# bass_filter.net
KiCad netlist of a schematic drawn in EAGLE
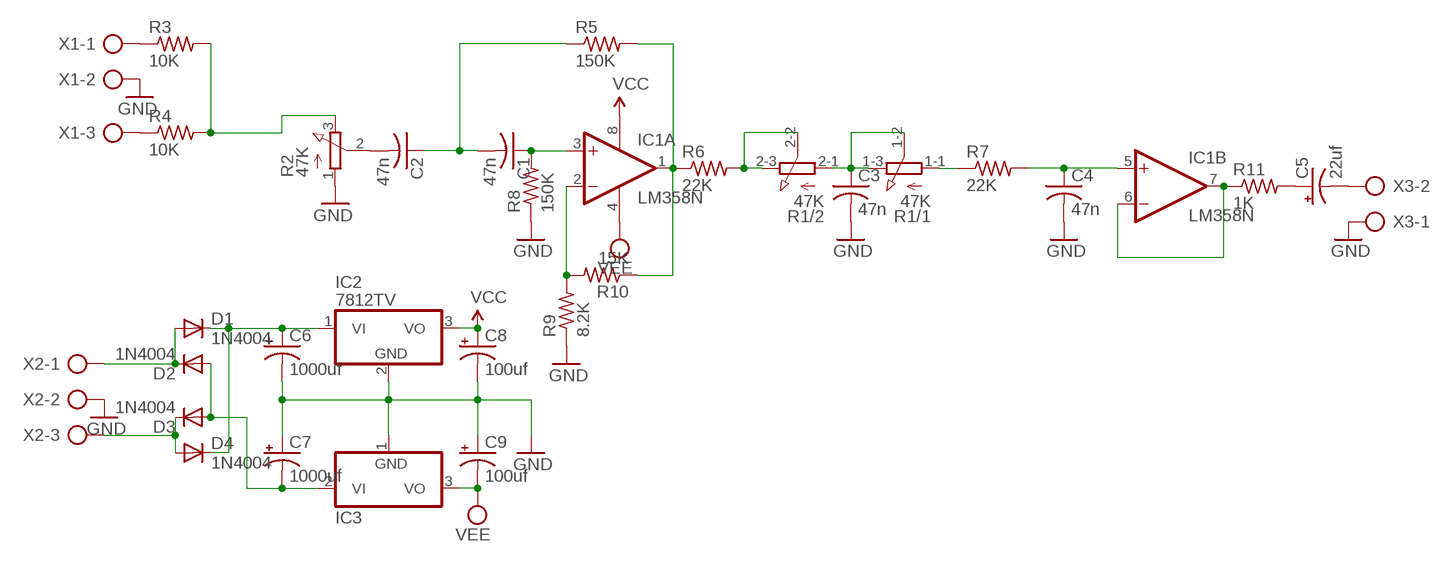
[diagram p0: schematic, sheet 1]

(export (version "E")
  (design (tool "Eeschema 10.0.6"))
  (components
    (comp (ref "C1")
      (value "47n")
      (footprint "eagle-import:C050-045X075")
      (libsource (lib "eagle-import") (part "C-US050-045X075"))
    )
    (comp (ref "C2")
      (value "47n")
      (footprint "eagle-import:C050-045X075")
      (libsource (lib "eagle-import") (part "C-US050-045X075"))
    )
    (comp (ref "C3")
      (value "47n")
      (footprint "eagle-import:C050-045X075")
      (libsource (lib "eagle-import") (part "C-US050-045X075"))
    )
    (comp (ref "C4")
      (value "47n")
      (footprint "eagle-import:C050-045X075")
      (libsource (lib "eagle-import") (part "C-US050-045X075"))
    )
    (comp (ref "C5")
      (value "22uf")
      (footprint "eagle-import:E2,5-6E")
      (libsource (lib "eagle-import") (part "CPOL-USE2,5-6E"))
    )
    (comp (ref "C6")
      (value "1000uf")
      (footprint "eagle-import:E5-13")
      (libsource (lib "eagle-import") (part "CPOL-USE5-13"))
    )
    (comp (ref "C7")
      (value "1000uf")
      (footprint "eagle-import:E5-13")
      (libsource (lib "eagle-import") (part "CPOL-USE5-13"))
    )
    (comp (ref "C8")
      (value "100uf")
      (footprint "eagle-import:E2,5-6")
      (libsource (lib "eagle-import") (part "CPOL-USE2.5-6"))
    )
    (comp (ref "C9")
      (value "100uf")
      (footprint "eagle-import:E2,5-6")
      (libsource (lib "eagle-import") (part "CPOL-USE2.5-6"))
    )
    (comp (ref "D1")
      (value "1N4004")
      (footprint "eagle-import:DO41-10")
      (libsource (lib "eagle-import") (part "1N4004"))
    )
    (comp (ref "D2")
      (value "1N4004")
      (footprint "eagle-import:DO41-10")
      (libsource (lib "eagle-import") (part "1N4004"))
    )
    (comp (ref "D3")
      (value "1N4004")
      (footprint "eagle-import:DO41-10")
      (libsource (lib "eagle-import") (part "1N4004"))
    )
    (comp (ref "D4")
      (value "1N4004")
      (footprint "eagle-import:DO41-10")
      (libsource (lib "eagle-import") (part "1N4004"))
    )
    (comp (ref "IC1")
      (value "LM358N")
      (footprint "eagle-import:DIL08")
      (libsource (lib "eagle-import") (part "LM358N"))
    )
    (comp (ref "IC2")
      (value "7812TV")
      (footprint "eagle-import:TO220V")
      (libsource (lib "eagle-import") (part "78TV12"))
    )
    (comp (ref "IC3")
      (value "7912T")
      (footprint "eagle-import:TO220H")
      (libsource (lib "eagle-import") (part "79T12"))
    )
    (comp (ref "R1")
      (value "47K")
      (footprint "eagle-import:3RP_1610G")
      (libsource (lib "eagle-import") (part "3RP/1610G"))
    )
    (comp (ref "R2")
      (value "47K")
      (footprint "eagle-import:3RP_1610N")
      (libsource (lib "eagle-import") (part "3RP/1610N"))
    )
    (comp (ref "R3")
      (value "10K")
      (footprint "eagle-import:0805-THM")
      (libsource (lib "eagle-import") (part "FLIPFLOP-RES"))
    )
    (comp (ref "R4")
      (value "10K")
      (footprint "eagle-import:0805-THM")
      (libsource (lib "eagle-import") (part "FLIPFLOP-RES"))
    )
    (comp (ref "R5")
      (value "150K")
      (footprint "eagle-import:0805-THM")
      (libsource (lib "eagle-import") (part "FLIPFLOP-RES"))
    )
    (comp (ref "R6")
      (value "22K")
      (footprint "eagle-import:0805-THM")
      (libsource (lib "eagle-import") (part "FLIPFLOP-RES"))
    )
    (comp (ref "R7")
      (value "22K")
      (footprint "eagle-import:0805-THM")
      (libsource (lib "eagle-import") (part "FLIPFLOP-RES"))
    )
    (comp (ref "R8")
      (value "150K")
      (footprint "eagle-import:0805-THM")
      (libsource (lib "eagle-import") (part "FLIPFLOP-RES"))
    )
    (comp (ref "R9")
      (value "8.2K")
      (footprint "eagle-import:0805-THM")
      (libsource (lib "eagle-import") (part "FLIPFLOP-RES"))
    )
    (comp (ref "R10")
      (value "15K")
      (footprint "eagle-import:0805-THM")
      (libsource (lib "eagle-import") (part "FLIPFLOP-RES"))
    )
    (comp (ref "R11")
      (value "1K")
      (footprint "eagle-import:0805-THM")
      (libsource (lib "eagle-import") (part "FLIPFLOP-RES"))
    )
    (comp (ref "X1")
      (value "AK300/3")
      (footprint "eagle-import:AK300_3")
      (libsource (lib "eagle-import") (part "AK300/3"))
    )
    (comp (ref "X2")
      (value "AK300/3")
      (footprint "eagle-import:AK300_3")
      (libsource (lib "eagle-import") (part "AK300/3"))
    )
    (comp (ref "X3")
      (value "AK300/2")
      (footprint "eagle-import:AK300_2")
      (libsource (lib "eagle-import") (part "AK300/2"))
    )
  )
  (nets
    (net (code "1") (name "GND") (class "Default")
      (node (ref "C3") (pin "2") (pinfunction "2_2") (pintype "passive"))
      (node (ref "C4") (pin "2") (pinfunction "2_2") (pintype "passive"))
      (node (ref "C6") (pin "-") (pinfunction "-_-") (pintype "passive"))
      (node (ref "C7") (pin "+") (pinfunction "+_+") (pintype "passive"))
      (node (ref "C8") (pin "-") (pinfunction "-_-") (pintype "passive"))
      (node (ref "C9") (pin "+") (pinfunction "+_+") (pintype "passive"))
      (node (ref "IC2") (pin "2") (pinfunction "GND_2") (pintype "passive"))
      (node (ref "IC3") (pin "1") (pinfunction "GND_1") (pintype "passive"))
      (node (ref "R2") (pin "1") (pinfunction "A_1") (pintype "passive"))
      (node (ref "R8") (pin "1") (pinfunction "1_1") (pintype "passive"))
      (node (ref "R9") (pin "1") (pinfunction "1_1") (pintype "passive"))
      (node (ref "X1") (pin "2") (pinfunction "KL_2") (pintype "passive"))
      (node (ref "X2") (pin "2") (pinfunction "KL_2") (pintype "passive"))
      (node (ref "X3") (pin "1") (pinfunction "KL_1") (pintype "passive"))
    )
    (net (code "2") (name "Net-(C1-Pad2)") (class "Default")
      (node (ref "C1") (pin "2") (pinfunction "2_2") (pintype "passive"))
      (node (ref "C2") (pin "1") (pinfunction "1_1") (pintype "passive"))
      (node (ref "R5") (pin "1") (pinfunction "1_1") (pintype "passive"))
    )
    (net (code "3") (name "Net-(C5-Pad+)") (class "Default")
      (node (ref "C5") (pin "+") (pinfunction "+_+") (pintype "passive"))
      (node (ref "R11") (pin "2") (pinfunction "2_2") (pintype "passive"))
    )
    (net (code "4") (name "Net-(IC1A-+IN)") (class "Default")
      (node (ref "C1") (pin "1") (pinfunction "1_1") (pintype "passive"))
      (node (ref "IC1") (pin "3") (pinfunction "+IN_3") (pintype "input"))
      (node (ref "R8") (pin "2") (pinfunction "2_2") (pintype "passive"))
    )
    (net (code "5") (name "Net-(IC1A--IN)") (class "Default")
      (node (ref "IC1") (pin "2") (pinfunction "-IN_2") (pintype "input"))
      (node (ref "R10") (pin "2") (pinfunction "2_2") (pintype "passive"))
      (node (ref "R9") (pin "2") (pinfunction "2_2") (pintype "passive"))
    )
    (net (code "6") (name "Net-(IC1A-OUT)") (class "Default")
      (node (ref "IC1") (pin "1") (pinfunction "OUT_1") (pintype "output"))
      (node (ref "R10") (pin "1") (pinfunction "1_1") (pintype "passive"))
      (node (ref "R5") (pin "2") (pinfunction "2_2") (pintype "passive"))
      (node (ref "R6") (pin "1") (pinfunction "1_1") (pintype "passive"))
    )
    (net (code "7") (name "Net-(IC1B-+IN)") (class "Default")
      (node (ref "C4") (pin "1") (pinfunction "1_1") (pintype "passive"))
      (node (ref "IC1") (pin "5") (pinfunction "+IN_5") (pintype "input"))
      (node (ref "R7") (pin "2") (pinfunction "2_2") (pintype "passive"))
    )
    (net (code "8") (name "Net-(IC1B--IN)") (class "Default")
      (node (ref "IC1") (pin "6") (pinfunction "-IN_6") (pintype "input"))
      (node (ref "IC1") (pin "7") (pinfunction "OUT_7") (pintype "output"))
      (node (ref "R11") (pin "1") (pinfunction "1_1") (pintype "passive"))
    )
    (net (code "9") (name "Net-(IC2-VI)") (class "Default")
      (node (ref "C6") (pin "+") (pinfunction "+_+") (pintype "passive"))
      (node (ref "D1") (pin "C") (pinfunction "C_C") (pintype "passive"))
      (node (ref "D4") (pin "C") (pinfunction "C_C") (pintype "passive"))
      (node (ref "IC2") (pin "1") (pinfunction "VI_1") (pintype "input"))
    )
    (net (code "10") (name "Net-(IC3-VI)") (class "Default")
      (node (ref "C7") (pin "-") (pinfunction "-_-") (pintype "passive"))
      (node (ref "D2") (pin "A") (pinfunction "A_A") (pintype "passive"))
      (node (ref "D3") (pin "A") (pinfunction "A_A") (pintype "passive"))
      (node (ref "IC3") (pin "2") (pinfunction "VI_2") (pintype "input"))
    )
    (net (code "11") (name "Net-(R1A-A)") (class "Default")
      (node (ref "R1") (pin "1-1") (pinfunction "A_1-1") (pintype "passive"))
      (node (ref "R7") (pin "1") (pinfunction "1_1") (pintype "passive"))
    )
    (net (code "12") (name "Net-(R1A-E)") (class "Default")
      (node (ref "C3") (pin "1") (pinfunction "1_1") (pintype "passive"))
      (node (ref "R1") (pin "1-2") (pinfunction "S_1-2") (pintype "passive"))
      (node (ref "R1") (pin "1-3") (pinfunction "E_1-3") (pintype "passive"))
      (node (ref "R1") (pin "2-1") (pinfunction "A_2-1") (pintype "passive"))
    )
    (net (code "13") (name "Net-(R1B-E)") (class "Default")
      (node (ref "R1") (pin "2-2") (pinfunction "S_2-2") (pintype "passive"))
      (node (ref "R1") (pin "2-3") (pinfunction "E_2-3") (pintype "passive"))
      (node (ref "R6") (pin "2") (pinfunction "2_2") (pintype "passive"))
    )
    (net (code "14") (name "Net-(R2-E)") (class "Default")
      (node (ref "R2") (pin "3") (pinfunction "E_3") (pintype "passive"))
      (node (ref "R3") (pin "2") (pinfunction "2_2") (pintype "passive"))
      (node (ref "R4") (pin "2") (pinfunction "2_2") (pintype "passive"))
    )
    (net (code "15") (name "Net-(R2-S)") (class "Default")
      (node (ref "C2") (pin "2") (pinfunction "2_2") (pintype "passive"))
      (node (ref "R2") (pin "2") (pinfunction "S_2") (pintype "passive"))
    )
    (net (code "16") (name "Net-(X1A-KL)") (class "Default")
      (node (ref "R3") (pin "1") (pinfunction "1_1") (pintype "passive"))
      (node (ref "X1") (pin "1") (pinfunction "KL_1") (pintype "passive"))
    )
    (net (code "17") (name "Net-(X1C-KL)") (class "Default")
      (node (ref "R4") (pin "1") (pinfunction "1_1") (pintype "passive"))
      (node (ref "X1") (pin "3") (pinfunction "KL_3") (pintype "passive"))
    )
    (net (code "18") (name "Net-(X2A-KL)") (class "Default")
      (node (ref "D1") (pin "A") (pinfunction "A_A") (pintype "passive"))
      (node (ref "D2") (pin "C") (pinfunction "C_C") (pintype "passive"))
      (node (ref "X2") (pin "1") (pinfunction "KL_1") (pintype "passive"))
    )
    (net (code "19") (name "Net-(X2C-KL)") (class "Default")
      (node (ref "D3") (pin "C") (pinfunction "C_C") (pintype "passive"))
      (node (ref "D4") (pin "A") (pinfunction "A_A") (pintype "passive"))
      (node (ref "X2") (pin "3") (pinfunction "KL_3") (pintype "passive"))
    )
    (net (code "20") (name "Net-(X3B-KL)") (class "Default")
      (node (ref "C5") (pin "-") (pinfunction "-_-") (pintype "passive"))
      (node (ref "X3") (pin "2") (pinfunction "KL_2") (pintype "passive"))
    )
    (net (code "21") (name "VCC") (class "Default")
      (node (ref "C8") (pin "+") (pinfunction "+_+") (pintype "passive"))
      (node (ref "IC1") (pin "8") (pinfunction "V+_8") (pintype "power_in"))
      (node (ref "IC2") (pin "3") (pinfunction "VO_3") (pintype "passive"))
    )
    (net (code "22") (name "VEE") (class "Default")
      (node (ref "C9") (pin "-") (pinfunction "-_-") (pintype "passive"))
      (node (ref "IC1") (pin "4") (pinfunction "V-_4") (pintype "power_in"))
      (node (ref "IC3") (pin "3") (pinfunction "VO_3") (pintype "passive"))
    )
  )
)
